# NanoV3_3.net
KiCad netlist of a schematic drawn in EAGLE
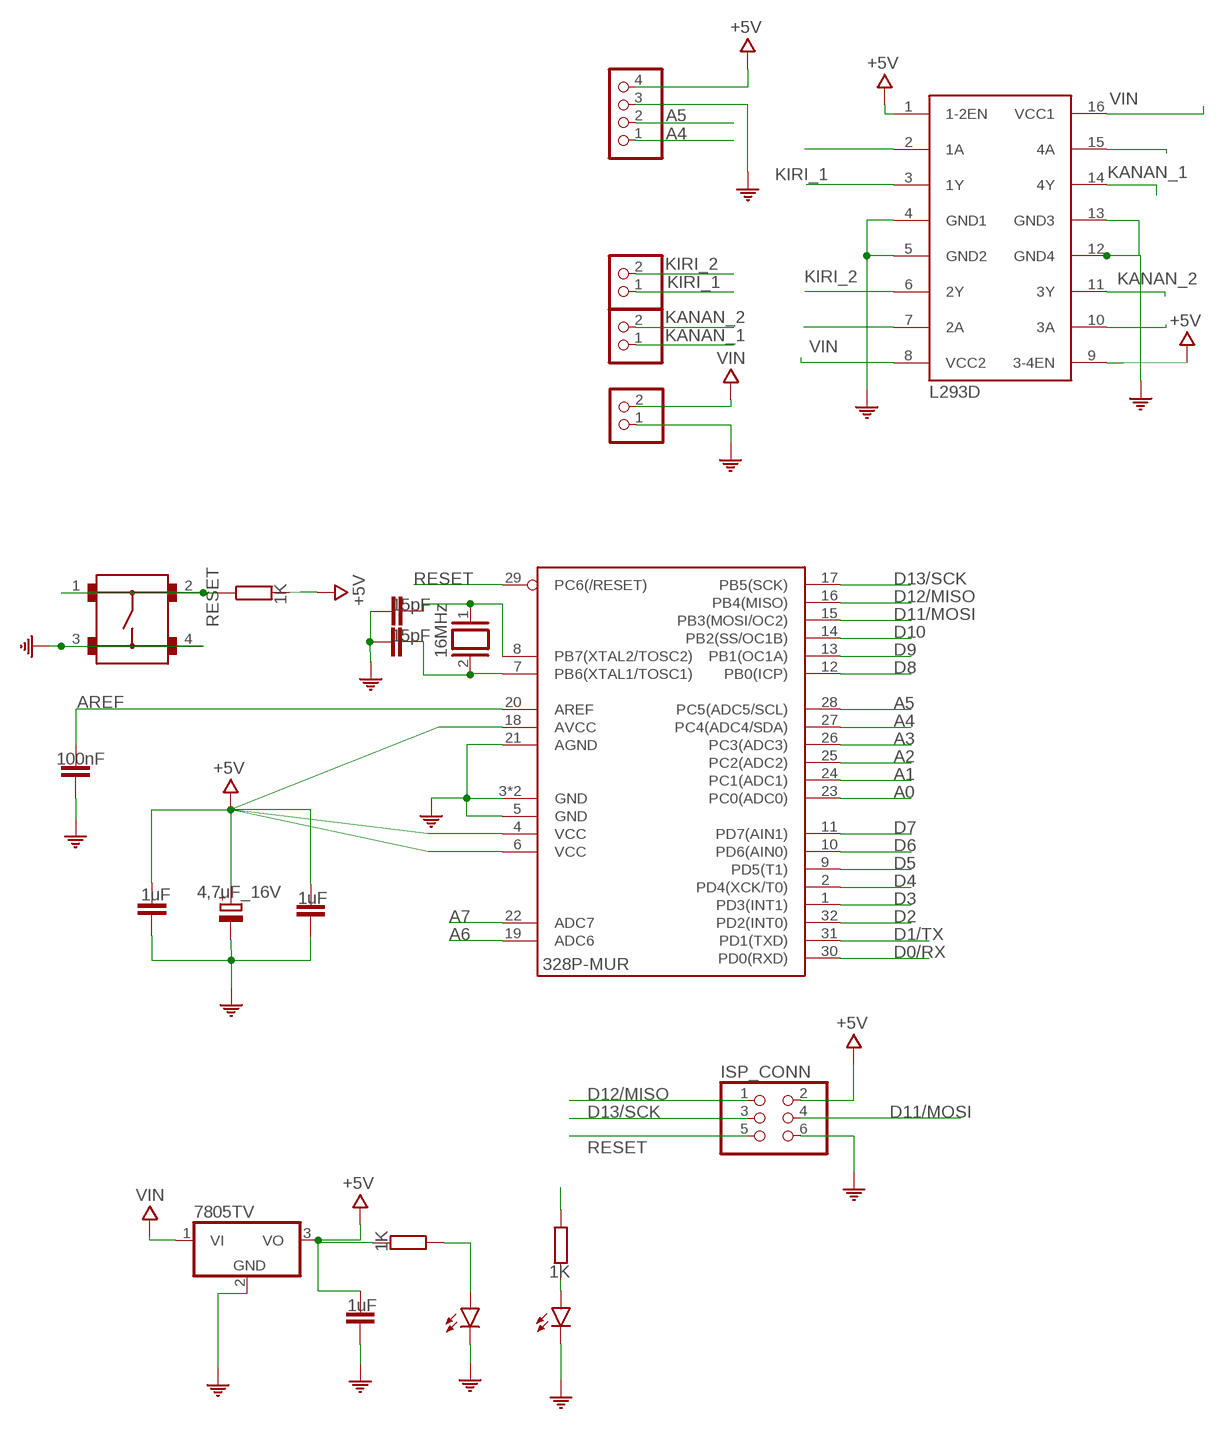
[diagram p0: schematic, sheet 1]

(export (version "E")
  (design (tool "Eeschema 10.0.6"))
  (components
    (comp (ref "C1")
      (value "4,7uF_16V")
      (footprint "eagle-import:B45181A")
      (libsource (lib "eagle-import") (part "CPOL-EUB45181A"))
    )
    (comp (ref "C2")
      (value "15pF")
      (footprint "eagle-import:C025-024X044")
      (libsource (lib "eagle-import") (part "C-EU025-024X044"))
    )
    (comp (ref "C3")
      (value "1uF")
      (footprint "eagle-import:C025-024X044")
      (libsource (lib "eagle-import") (part "C-EU025-024X044"))
    )
    (comp (ref "C4")
      (value "15pF")
      (footprint "eagle-import:C025-024X044")
      (libsource (lib "eagle-import") (part "C-EU025-024X044"))
    )
    (comp (ref "C6")
      (value "100nF")
      (footprint "eagle-import:C025-024X044")
      (libsource (lib "eagle-import") (part "C-EU025-024X044"))
    )
    (comp (ref "C9")
      (value "1uF")
      (footprint "eagle-import:C025-024X044")
      (libsource (lib "eagle-import") (part "C-EU025-024X044"))
    )
    (comp (ref "C10")
      (value "1uF")
      (footprint "eagle-import:C025-024X044")
      (libsource (lib "eagle-import") (part "C-EU025-024X044"))
    )
    (comp (ref "GYRO")
      (value "PINHD-1X4")
      (footprint "eagle-import:1X04")
      (libsource (lib "eagle-import") (part "PINHD-1X4"))
    )
    (comp (ref "IC1")
      (value "L293D")
      (footprint "eagle-import:DIL16")
      (libsource (lib "eagle-import") (part "L293D"))
    )
    (comp (ref "IC3")
      (value "328P-MUR")
      (footprint "eagle-import:VQFN32")
      (fields (field (name "MANUFACTURER") "ATMEL"))
      (libsource (lib "eagle-import") (part "ATMEGA328P-32MUR"))
    )
    (comp (ref "IC4")
      (value "7805TV")
      (footprint "eagle-import:TO220V")
      (libsource (lib "eagle-import") (part "78TV05"))
    )
    (comp (ref "ISP_CONN")
      (value "0114_PH254-203DF118A00V")
      (footprint "eagle-import:2X03")
      (fields (field (name "PART_NUMBER") "PH254-203DF118A00V"))
      (libsource (lib "eagle-import") (part "0114_PH254-203DF118A00V"))
    )
    (comp (ref "J3")
      (value "INPUT")
      (footprint "eagle-import:1X02")
      (libsource (lib "eagle-import") (part "PINHD-1X2"))
    )
    (comp (ref "J6")
      (value "MOTOR")
      (footprint "eagle-import:1X02")
      (libsource (lib "eagle-import") (part "PINHD-1X2"))
    )
    (comp (ref "L")
      (value "DATA")
      (footprint "eagle-import:LED3MM")
      (libsource (lib "eagle-import") (part "LED3MM"))
    )
    (comp (ref "MOTOR")
      (value "MOTOR")
      (footprint "eagle-import:1X02")
      (libsource (lib "eagle-import") (part "PINHD-1X2"))
    )
    (comp (ref "PWR")
      (value "POWER")
      (footprint "eagle-import:LED3MM")
      (libsource (lib "eagle-import") (part "LED3MM"))
    )
    (comp (ref "Q1")
      (value "16MHz")
      (footprint "eagle-import:QS")
      (libsource (lib "eagle-import") (part "XTAL/S"))
    )
    (comp (ref "R1")
      (value "1K")
      (footprint "eagle-import:0204_5")
      (libsource (lib "eagle-import") (part "R-EU_0204/5"))
    )
    (comp (ref "R2")
      (value "1K")
      (footprint "eagle-import:0204_5")
      (libsource (lib "eagle-import") (part "R-EU_0204/5"))
    )
    (comp (ref "R3")
      (value "1K")
      (footprint "eagle-import:0204_5")
      (libsource (lib "eagle-import") (part "R-EU_0204/5"))
    )
    (comp (ref "SW1")
      (value "RESET")
      (footprint "eagle-import:B3F-1000")
      (fields
        (field (name "DIGI_KEY_PART_NUMBER") "SW400-ND")
        (field (name "MANUFACTURER") "Omron Electronics Inc-EMC Div")
        (field (name "MPN") "B3F-1000")
        (field (name "CREATED_BY") "PCBLayout.com")
      )
      (libsource (lib "eagle-import") (part "B3F-1000"))
    )
  )
  (nets
    (net (code "1") (name "+5V") (class "Default")
      (node (ref "C1") (pin "+") (pinfunction "+_+") (pintype "passive"))
      (node (ref "C10") (pin "2") (pinfunction "2_2") (pintype "passive"))
      (node (ref "C3") (pin "2") (pinfunction "2_2") (pintype "passive"))
      (node (ref "C9") (pin "2") (pinfunction "2_2") (pintype "passive"))
      (node (ref "GYRO") (pin "4") (pinfunction "4_4") (pintype "passive"))
      (node (ref "IC1") (pin "1") (pinfunction "1-2EN_1") (pintype "input"))
      (node (ref "IC1") (pin "9") (pinfunction "3-4EN_9") (pintype "input"))
      (node (ref "IC3") (pin "18") (pinfunction "AVCC_18") (pintype "bidirectional"))
      (node (ref "IC3") (pin "4") (pinfunction "VCC_4") (pintype "bidirectional"))
      (node (ref "IC3") (pin "6") (pinfunction "VCC_6") (pintype "bidirectional"))
      (node (ref "IC4") (pin "3") (pinfunction "VO_3") (pintype "passive"))
      (node (ref "ISP_CONN") (pin "2") (pinfunction "2_2") (pintype "passive"))
      (node (ref "R1") (pin "2") (pinfunction "2_2") (pintype "passive"))
      (node (ref "R2") (pin "2") (pinfunction "2_2") (pintype "passive"))
    )
    (net (code "2") (name "/A0") (class "Default")
      (node (ref "IC3") (pin "23") (pinfunction "PC0(ADC0)_23") (pintype "bidirectional"))
    )
    (net (code "3") (name "/A1") (class "Default")
      (node (ref "IC3") (pin "24") (pinfunction "PC1(ADC1)_24") (pintype "bidirectional"))
    )
    (net (code "4") (name "/A2") (class "Default")
      (node (ref "IC3") (pin "25") (pinfunction "PC2(ADC2)_25") (pintype "bidirectional"))
    )
    (net (code "5") (name "/A3") (class "Default")
      (node (ref "IC3") (pin "26") (pinfunction "PC3(ADC3)_26") (pintype "bidirectional"))
    )
    (net (code "6") (name "/A4") (class "Default")
      (node (ref "GYRO") (pin "1") (pinfunction "1_1") (pintype "passive"))
      (node (ref "IC3") (pin "27") (pinfunction "PC4(ADC4/SDA)_27") (pintype "bidirectional"))
    )
    (net (code "7") (name "/A5") (class "Default")
      (node (ref "GYRO") (pin "2") (pinfunction "2_2") (pintype "passive"))
      (node (ref "IC3") (pin "28") (pinfunction "PC5(ADC5/SCL)_28") (pintype "bidirectional"))
    )
    (net (code "8") (name "/A6") (class "Default")
      (node (ref "IC3") (pin "19") (pinfunction "ADC6_19") (pintype "bidirectional"))
    )
    (net (code "9") (name "/A7") (class "Default")
      (node (ref "IC3") (pin "22") (pinfunction "ADC7_22") (pintype "bidirectional"))
    )
    (net (code "10") (name "/AREF") (class "Default")
      (node (ref "C6") (pin "1") (pinfunction "1_1") (pintype "passive"))
      (node (ref "IC3") (pin "20") (pinfunction "AREF_20") (pintype "bidirectional"))
    )
    (net (code "11") (name "/D0{slash}RX") (class "Default")
      (node (ref "IC3") (pin "30") (pinfunction "PD0(RXD)_30") (pintype "bidirectional"))
    )
    (net (code "12") (name "/D1{slash}TX") (class "Default")
      (node (ref "IC3") (pin "31") (pinfunction "PD1(TXD)_31") (pintype "bidirectional"))
    )
    (net (code "13") (name "/D2") (class "Default")
      (node (ref "IC3") (pin "32") (pinfunction "PD2(INT0)_32") (pintype "bidirectional"))
    )
    (net (code "14") (name "/D3") (class "Default")
      (node (ref "IC3") (pin "1") (pinfunction "PD3(INT1)_1") (pintype "bidirectional"))
    )
    (net (code "15") (name "/D4") (class "Default")
      (node (ref "IC3") (pin "2") (pinfunction "PD4(XCK/T0)_2") (pintype "bidirectional"))
    )
    (net (code "16") (name "/D5") (class "Default")
      (node (ref "IC3") (pin "9") (pinfunction "PD5(T1)_9") (pintype "bidirectional"))
    )
    (net (code "17") (name "/D6") (class "Default")
      (node (ref "IC1") (pin "2") (pinfunction "1A_2") (pintype "input"))
      (node (ref "IC3") (pin "10") (pinfunction "PD6(AIN0)_10") (pintype "bidirectional"))
    )
    (net (code "18") (name "/D7") (class "Default")
      (node (ref "IC3") (pin "11") (pinfunction "PD7(AIN1)_11") (pintype "bidirectional"))
    )
    (net (code "19") (name "/D8") (class "Default")
      (node (ref "IC3") (pin "12") (pinfunction "PB0(ICP)_12") (pintype "bidirectional"))
    )
    (net (code "20") (name "/D9") (class "Default")
      (node (ref "IC1") (pin "7") (pinfunction "2A_7") (pintype "input"))
      (node (ref "IC3") (pin "13") (pinfunction "PB1(OC1A)_13") (pintype "bidirectional"))
    )
    (net (code "21") (name "/D10") (class "Default")
      (node (ref "IC1") (pin "10") (pinfunction "3A_10") (pintype "input"))
      (node (ref "IC3") (pin "14") (pinfunction "PB2(SS/OC1B)_14") (pintype "bidirectional"))
    )
    (net (code "22") (name "/D11{slash}MOSI") (class "Default")
      (node (ref "IC1") (pin "15") (pinfunction "4A_15") (pintype "input"))
      (node (ref "IC3") (pin "15") (pinfunction "PB3(MOSI/OC2)_15") (pintype "bidirectional"))
      (node (ref "ISP_CONN") (pin "4") (pinfunction "4_4") (pintype "passive"))
    )
    (net (code "23") (name "/D12{slash}MISO") (class "Default")
      (node (ref "IC3") (pin "16") (pinfunction "PB4(MISO)_16") (pintype "bidirectional"))
      (node (ref "ISP_CONN") (pin "1") (pinfunction "1_1") (pintype "passive"))
    )
    (net (code "24") (name "/D13{slash}SCK") (class "Default")
      (node (ref "IC3") (pin "17") (pinfunction "PB5(SCK)_17") (pintype "bidirectional"))
      (node (ref "ISP_CONN") (pin "3") (pinfunction "3_3") (pintype "passive"))
      (node (ref "R3") (pin "1") (pinfunction "1_1") (pintype "passive"))
    )
    (net (code "25") (name "/KANAN_1") (class "Default")
      (node (ref "IC1") (pin "14") (pinfunction "4Y_14") (pintype "output"))
      (node (ref "J6") (pin "1") (pinfunction "1_1") (pintype "passive"))
    )
    (net (code "26") (name "/KANAN_2") (class "Default")
      (node (ref "IC1") (pin "11") (pinfunction "3Y_11") (pintype "output"))
      (node (ref "J6") (pin "2") (pinfunction "2_2") (pintype "passive"))
    )
    (net (code "27") (name "/KIRI_1") (class "Default")
      (node (ref "IC1") (pin "3") (pinfunction "1Y_3") (pintype "output"))
      (node (ref "MOTOR") (pin "1") (pinfunction "1_1") (pintype "passive"))
    )
    (net (code "28") (name "/KIRI_2") (class "Default")
      (node (ref "IC1") (pin "6") (pinfunction "2Y_6") (pintype "output"))
      (node (ref "MOTOR") (pin "2") (pinfunction "2_2") (pintype "passive"))
    )
    (net (code "29") (name "/RESET") (class "Default")
      (node (ref "IC3") (pin "29") (pinfunction "PC6(/RESET)_29") (pintype "bidirectional"))
      (node (ref "ISP_CONN") (pin "5") (pinfunction "5_5") (pintype "passive"))
      (node (ref "R1") (pin "1") (pinfunction "1_1") (pintype "passive"))
      (node (ref "SW1") (pin "1") (pinfunction "1_1") (pintype "passive"))
      (node (ref "SW1") (pin "2") (pinfunction "2_2") (pintype "passive"))
    )
    (net (code "30") (name "COM") (class "Default")
      (node (ref "C1") (pin "-") (pinfunction "-_-") (pintype "passive"))
      (node (ref "C10") (pin "1") (pinfunction "1_1") (pintype "passive"))
      (node (ref "C2") (pin "1") (pinfunction "1_1") (pintype "passive"))
      (node (ref "C3") (pin "1") (pinfunction "1_1") (pintype "passive"))
      (node (ref "C4") (pin "1") (pinfunction "1_1") (pintype "passive"))
      (node (ref "C6") (pin "2") (pinfunction "2_2") (pintype "passive"))
      (node (ref "C9") (pin "1") (pinfunction "1_1") (pintype "passive"))
      (node (ref "GYRO") (pin "3") (pinfunction "3_3") (pintype "passive"))
      (node (ref "IC1") (pin "12") (pinfunction "GND4_12") (pintype "power_in"))
      (node (ref "IC1") (pin "13") (pinfunction "GND3_13") (pintype "power_in"))
      (node (ref "IC1") (pin "4") (pinfunction "GND1_4") (pintype "power_in"))
      (node (ref "IC1") (pin "5") (pinfunction "GND2_5") (pintype "power_in"))
      (node (ref "IC3") (pin "21") (pinfunction "AGND_21") (pintype "bidirectional"))
      (node (ref "IC3") (pin "3") (pinfunction "GND_3") (pintype "bidirectional"))
      (node (ref "IC3") (pin "33") (pinfunction "GND_33") (pintype "bidirectional"))
      (node (ref "IC3") (pin "5") (pinfunction "GND_5") (pintype "bidirectional"))
      (node (ref "IC4") (pin "2") (pinfunction "GND_2") (pintype "passive"))
      (node (ref "ISP_CONN") (pin "6") (pinfunction "6_6") (pintype "passive"))
      (node (ref "J3") (pin "1") (pinfunction "1_1") (pintype "passive"))
      (node (ref "L") (pin "K") (pinfunction "C_K") (pintype "passive"))
      (node (ref "PWR") (pin "K") (pinfunction "C_K") (pintype "passive"))
      (node (ref "SW1") (pin "3") (pinfunction "3_3") (pintype "passive"))
      (node (ref "SW1") (pin "4") (pinfunction "4_4") (pintype "passive"))
    )
    (net (code "31") (name "Net-(IC3-PB6(XTAL1{slash}TOSC1))") (class "Default")
      (node (ref "C4") (pin "2") (pinfunction "2_2") (pintype "passive"))
      (node (ref "IC3") (pin "7") (pinfunction "PB6(XTAL1/TOSC1)_7") (pintype "bidirectional"))
      (node (ref "Q1") (pin "2") (pinfunction "2_2") (pintype "passive"))
    )
    (net (code "32") (name "Net-(IC3-PB7(XTAL2{slash}TOSC2))") (class "Default")
      (node (ref "C2") (pin "2") (pinfunction "2_2") (pintype "passive"))
      (node (ref "IC3") (pin "8") (pinfunction "PB7(XTAL2/TOSC2)_8") (pintype "bidirectional"))
      (node (ref "Q1") (pin "1") (pinfunction "1_1") (pintype "passive"))
    )
    (net (code "33") (name "Net-(L-PadA)") (class "Default")
      (node (ref "L") (pin "A") (pinfunction "A_A") (pintype "passive"))
      (node (ref "R3") (pin "2") (pinfunction "2_2") (pintype "passive"))
    )
    (net (code "34") (name "Net-(PWR-PadA)") (class "Default")
      (node (ref "PWR") (pin "A") (pinfunction "A_A") (pintype "passive"))
      (node (ref "R2") (pin "1") (pinfunction "1_1") (pintype "passive"))
    )
    (net (code "35") (name "VIN") (class "Default")
      (node (ref "IC1") (pin "16") (pinfunction "VCC1_16") (pintype "power_in"))
      (node (ref "IC1") (pin "8") (pinfunction "VCC2_8") (pintype "power_in"))
      (node (ref "IC4") (pin "1") (pinfunction "VI_1") (pintype "input"))
      (node (ref "J3") (pin "2") (pinfunction "2_2") (pintype "passive"))
    )
  )
)
